# LPCB235_-_RM48_-_100BASET.net
KiCad netlist of a schematic drawn in Altium Designer
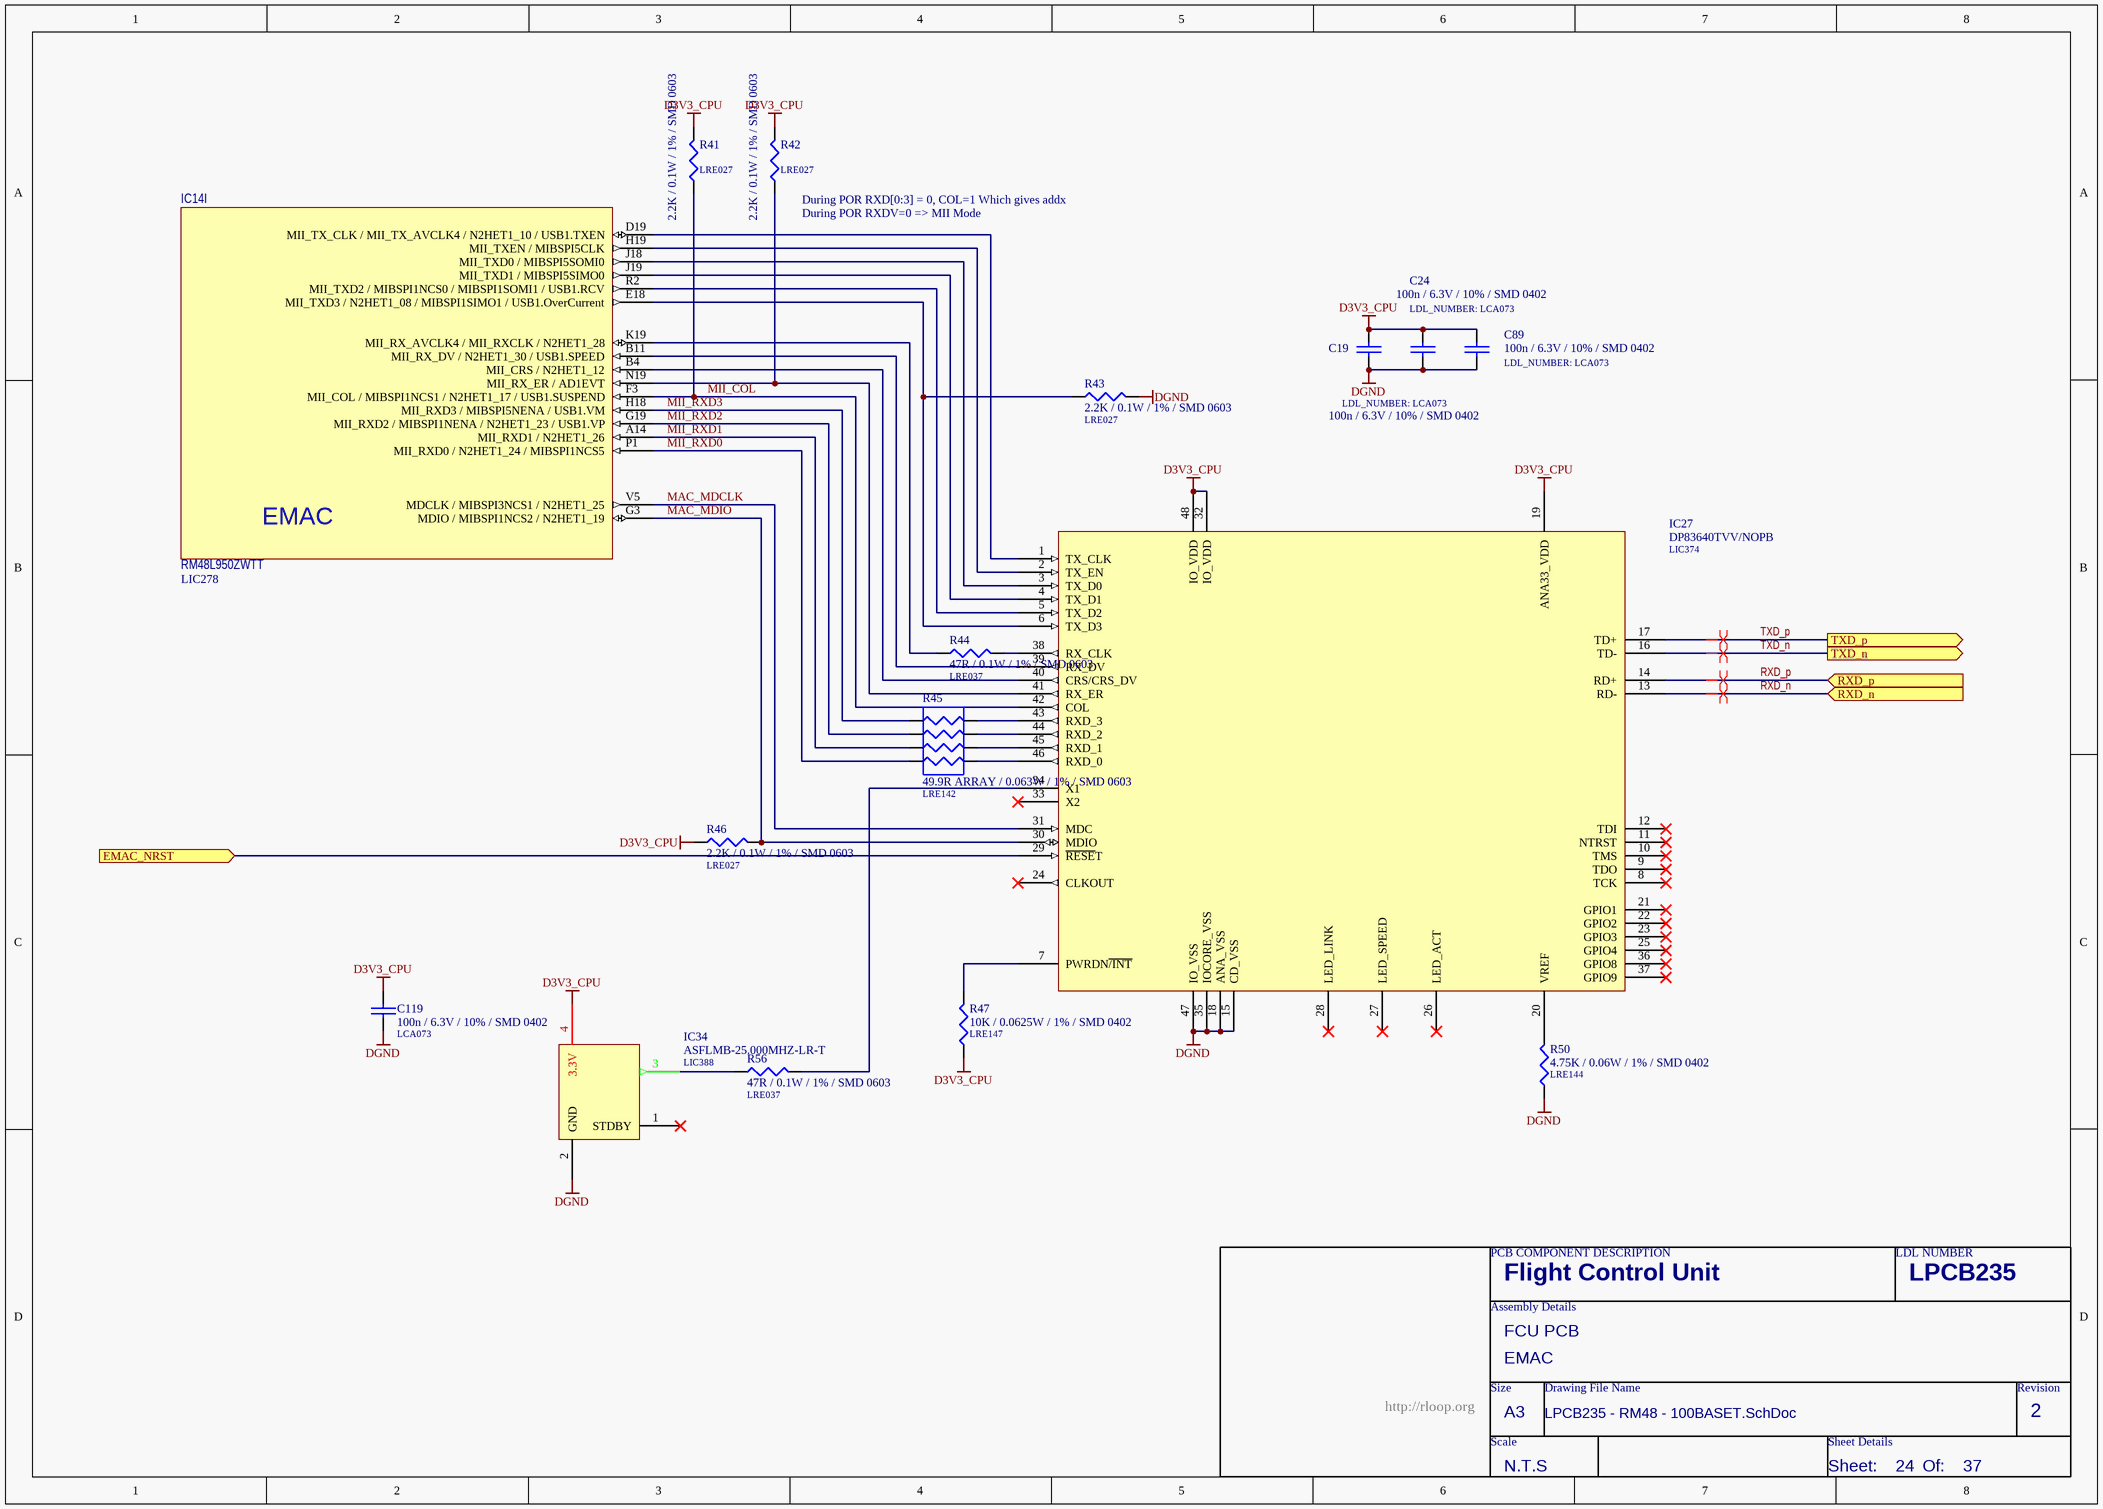
[diagram p0: LPCB235 - RM48 - 100BASET.SchDoc]

(export (version "E")
  (design (tool "Eeschema 10.0.6"))
  (components
    (comp (ref "C19")
      (value "100n / 6.3V / 10% / SMD 0402")
      (footprint "LFP012__CC1005-0402-IPC7351_B")
      (description "Capacitor, Ceramic Chip, 100nF (0.1uF), 6.3V, 10%, SMD 0402 [LCA073]")
      (fields (field (name "LDL_NUMBER") "LCA073"))
      (libsource (lib "LDL_Capacitors") (part "100n / 6.3V / 10% / SMD 0402"))
    )
    (comp (ref "C24")
      (value "100n / 6.3V / 10% / SMD 0402")
      (footprint "LFP012__CC1005-0402-IPC7351_B")
      (description "Capacitor, Ceramic Chip, 100nF (0.1uF), 6.3V, 10%, SMD 0402 [LCA073]")
      (fields (field (name "LDL_NUMBER") "LCA073"))
      (libsource (lib "LDL_Capacitors") (part "100n / 6.3V / 10% / SMD 0402"))
    )
    (comp (ref "C89")
      (value "100n / 6.3V / 10% / SMD 0402")
      (footprint "LFP012__CC1005-0402-IPC7351_B")
      (description "Capacitor, Ceramic Chip, 100nF (0.1uF), 6.3V, 10%, SMD 0402 [LCA073]")
      (fields (field (name "LDL_NUMBER") "LCA073"))
      (libsource (lib "LDL_Capacitors") (part "100n / 6.3V / 10% / SMD 0402"))
    )
    (comp (ref "C119")
      (value "100n / 6.3V / 10% / SMD 0402")
      (footprint "LFP012__CC1005-0402-IPC7351_B")
      (description "Capacitor, Ceramic Chip, 100nF (0.1uF), 6.3V, 10%, SMD 0402 [LCA073]")
      (fields (field (name "LDL_NUMBER") "LCA073"))
      (libsource (lib "LDL_Capacitors") (part "100n / 6.3V / 10% / SMD 0402"))
    )
    (comp (ref "IC14")
      (value "RM48L950ZWTT")
      (footprint "LFP054__ZWT (S-PBGA-N337)")
      (description "IC, CPU, RM48 Safety CPU, SMD NFBGA337 [LIC278]")
      (fields (field (name "LDL_NUMBER") "LIC278"))
      (libsource (lib "LDL_Semiconductors") (part "RM48L950ZWTT"))
    )
    (comp (ref "IC27")
      (value "DP83640TVV/NOPB")
      (footprint "LFP058__F-QFP7X7-G48")
      (description "IC, Ethernet Transceiver, Precision Real Time Protocol, SMD LQFP48 [LIC374]")
      (fields (field (name "LDL_NUMBER") "LIC374"))
      (libsource (lib "LDL_Semiconductors") (part "DP83640TVV/NOPB"))
    )
    (comp (ref "IC34")
      (value "ASFLMB-25.000MHZ-LR-T")
      (footprint "LFP072__ASFLMB")
      (description "IC, Oscillator Module, 25MHz, 3.3V, SMD [LIC388]")
      (fields (field (name "LDL_NUMBER") "LIC388"))
      (libsource (lib "LDL_Semiconductors") (part "ASFLMB-25.000MHZ-LR-T"))
    )
    (comp (ref "R41")
      (value "2.2K / 0.1W / 1% / SMD 0603")
      (footprint "LFP020__CR1608-0603-IPC7351_B")
      (description "Resistor, Ceramic Chip, 2.2K, 0.1W, 1%, SMD 0603 [LRE027]")
      (fields (field (name "LDL_NUMBER") "LRE027"))
      (libsource (lib "LDL_Resistors") (part "2.2K / 0.1W / 1% / SMD 0603"))
    )
    (comp (ref "R42")
      (value "2.2K / 0.1W / 1% / SMD 0603")
      (footprint "LFP020__CR1608-0603-IPC7351_B")
      (description "Resistor, Ceramic Chip, 2.2K, 0.1W, 1%, SMD 0603 [LRE027]")
      (fields (field (name "LDL_NUMBER") "LRE027"))
      (libsource (lib "LDL_Resistors") (part "2.2K / 0.1W / 1% / SMD 0603"))
    )
    (comp (ref "R43")
      (value "2.2K / 0.1W / 1% / SMD 0603")
      (footprint "LFP020__CR1608-0603-IPC7351_B")
      (description "Resistor, Ceramic Chip, 2.2K, 0.1W, 1%, SMD 0603 [LRE027]")
      (fields (field (name "LDL_NUMBER") "LRE027"))
      (libsource (lib "LDL_Resistors") (part "2.2K / 0.1W / 1% / SMD 0603"))
    )
    (comp (ref "R44")
      (value "47R / 0.1W / 1% / SMD 0603")
      (footprint "LFP020__CR1608-0603-IPC7351_B")
      (description "Resistor, Ceramic Chip, 47R, 0.1W, 1%, SMD 0603 [LRE037]")
      (fields (field (name "LDL_NUMBER") "LRE037"))
      (libsource (lib "LDL_Resistors") (part "47R / 0.1W / 1% / SMD 0603"))
    )
    (comp (ref "R45")
      (value "49.9R ARRAY / 0.063W / 1% / SMD 0603")
      (footprint "LFP065__RESPACK4-0603")
      (description "Resistor, Array, 49.9R, 0.063W, 1%, SMD 0603 [LRE142]")
      (fields (field (name "LDL_NUMBER") "LRE142"))
      (libsource (lib "LDL_Resistors") (part "49.9R ARRAY / 0.063W / 1% / SMD 0603"))
    )
    (comp (ref "R46")
      (value "2.2K / 0.1W / 1% / SMD 0603")
      (footprint "LFP020__CR1608-0603-IPC7351_B")
      (description "Resistor, Ceramic Chip, 2.2K, 0.1W, 1%, SMD 0603 [LRE027]")
      (fields (field (name "LDL_NUMBER") "LRE027"))
      (libsource (lib "LDL_Resistors") (part "2.2K / 0.1W / 1% / SMD 0603"))
    )
    (comp (ref "R47")
      (value "10K / 0.0625W / 1% / SMD 0402")
      (footprint "LFP030__CR1005-0402-IPC7351")
      (description "Resistor, Ceramic Chip, 10K, 0.0625W, 1%, SMD 0402 [LRE147]")
      (fields (field (name "LDL_NUMBER") "LRE147"))
      (libsource (lib "LDL_Resistors") (part "10K / 0.0625W / 1% / SMD 0402"))
    )
    (comp (ref "R50")
      (value "4.75K / 0.06W / 1% / SMD 0402")
      (footprint "LFP030__CR1005-0402-IPC7351")
      (description "Resistor, Ceramic Chip, 4.75K, 0.0625W, 1%, SMD 0402 [LRE144]")
      (fields (field (name "LDL_NUMBER") "LRE144"))
      (libsource (lib "LDL_Resistors") (part "4.75K / 0.06W / 1% / SMD 0402"))
    )
    (comp (ref "R56")
      (value "47R / 0.1W / 1% / SMD 0603")
      (footprint "LFP020__CR1608-0603-IPC7351_B")
      (description "Resistor, Ceramic Chip, 47R, 0.1W, 1%, SMD 0603 [LRE037]")
      (fields (field (name "LDL_NUMBER") "LRE037"))
      (libsource (lib "LDL_Resistors") (part "47R / 0.1W / 1% / SMD 0603"))
    )
  )
  (nets
    (net (code "1") (name "/EMAC_NRST") (class "Default")
      (node (ref "IC27") (pin "29") (pinfunction "~{RESE}T_29") (pintype "input"))
    )
    (net (code "2") (name "/MAC_MDCLK") (class "Default")
      (node (ref "IC14") (pin "V5") (pinfunction "MDCLK_/_MIBSPI3NCS1_/_N2HET1_25_V5") (pintype "output"))
      (node (ref "IC27") (pin "31") (pinfunction "MDC_31") (pintype "input"))
    )
    (net (code "3") (name "/MAC_MDIO") (class "Default")
      (node (ref "IC14") (pin "G3") (pinfunction "MDIO_/_MIBSPI1NCS2_/_N2HET1_19_G3") (pintype "bidirectional"))
      (node (ref "IC27") (pin "30") (pinfunction "MDIO_30") (pintype "bidirectional"))
      (node (ref "R46") (pin "2") (pintype "passive"))
    )
    (net (code "4") (name "/MII_COL") (class "Default")
      (node (ref "IC14") (pin "F3") (pinfunction "MII_COL_/_MIBSPI1NCS1_/_N2HET1_17_/_USB1.SUSPEND_F3") (pintype "input"))
      (node (ref "IC27") (pin "42") (pinfunction "COL_42") (pintype "output"))
      (node (ref "R41") (pin "1") (pintype "passive"))
    )
    (net (code "5") (name "/MII_RXD0") (class "Default")
      (node (ref "IC14") (pin "P1") (pinfunction "MII_RXD0_/_N2HET1_24_/_MIBSPI1NCS5_P1") (pintype "input"))
      (node (ref "R45") (pin "4") (pintype "passive"))
    )
    (net (code "6") (name "/MII_RXD1") (class "Default")
      (node (ref "IC14") (pin "A14") (pinfunction "MII_RXD1_/_N2HET1_26_A14") (pintype "input"))
      (node (ref "R45") (pin "3") (pintype "passive"))
    )
    (net (code "7") (name "/MII_RXD2") (class "Default")
      (node (ref "IC14") (pin "G19") (pinfunction "MII_RXD2_/_MIBSPI1NENA_/_N2HET1_23_/_USB1.VP_G19") (pintype "input"))
      (node (ref "R45") (pin "2") (pintype "passive"))
    )
    (net (code "8") (name "/MII_RXD3") (class "Default")
      (node (ref "IC14") (pin "H18") (pinfunction "MII_RXD3_/_MIBSPI5NENA_/_USB1.VM_H18") (pintype "input"))
      (node (ref "R45") (pin "1") (pintype "passive"))
    )
    (net (code "9") (name "/RXD_n") (class "Default")
      (node (ref "IC27") (pin "13") (pinfunction "RD-_13") (pintype "passive"))
    )
    (net (code "10") (name "/RXD_p") (class "Default")
      (node (ref "IC27") (pin "14") (pinfunction "RD+_14") (pintype "passive"))
    )
    (net (code "11") (name "/TXD_n") (class "Default")
      (node (ref "IC27") (pin "16") (pinfunction "TD-_16") (pintype "passive"))
    )
    (net (code "12") (name "/TXD_p") (class "Default")
      (node (ref "IC27") (pin "17") (pinfunction "TD+_17") (pintype "passive"))
    )
    (net (code "13") (name "D3V3_CPU") (class "Default")
      (node (ref "C119") (pin "1") (pintype "passive"))
      (node (ref "C19") (pin "1") (pintype "passive"))
      (node (ref "C24") (pin "1") (pintype "passive"))
      (node (ref "C89") (pin "1") (pintype "passive"))
      (node (ref "IC27") (pin "19") (pinfunction "ANA33_VDD_19") (pintype "power_in"))
      (node (ref "IC27") (pin "32") (pinfunction "IO_VDD_32") (pintype "power_in"))
      (node (ref "IC27") (pin "48") (pinfunction "IO_VDD_48") (pintype "power_in"))
      (node (ref "IC34") (pin "4") (pinfunction "3.3V_4") (pintype "power_in"))
      (node (ref "R41") (pin "2") (pintype "passive"))
      (node (ref "R42") (pin "2") (pintype "passive"))
      (node (ref "R46") (pin "1") (pintype "passive"))
      (node (ref "R47") (pin "1") (pintype "passive"))
    )
    (net (code "14") (name "DGND") (class "Default")
      (node (ref "C119") (pin "2") (pintype "passive"))
      (node (ref "C19") (pin "2") (pintype "passive"))
      (node (ref "C24") (pin "2") (pintype "passive"))
      (node (ref "C89") (pin "2") (pintype "passive"))
      (node (ref "IC27") (pin "15") (pinfunction "CD_VSS_15") (pintype "power_in"))
      (node (ref "IC27") (pin "18") (pinfunction "ANA_VSS_18") (pintype "power_in"))
      (node (ref "IC27") (pin "35") (pinfunction "IOCORE_VSS_35") (pintype "power_in"))
      (node (ref "IC27") (pin "47") (pinfunction "IO_VSS_47") (pintype "power_in"))
      (node (ref "IC34") (pin "2") (pinfunction "GND_2") (pintype "power_in"))
      (node (ref "R43") (pin "2") (pintype "passive"))
      (node (ref "R50") (pin "1") (pintype "passive"))
    )
    (net (code "15") (name "Net-(IC14I-MII_CRS_{slash}_N2HET1_12)") (class "Default")
      (node (ref "IC14") (pin "B4") (pinfunction "MII_CRS_/_N2HET1_12_B4") (pintype "input"))
      (node (ref "IC27") (pin "40") (pinfunction "CRS/CRS_DV_40") (pintype "output"))
    )
    (net (code "16") (name "Net-(IC14I-MII_RX_AVCLK4_{slash}_MII_RXCLK_{slash}_N2HET1_28)") (class "Default")
      (node (ref "IC14") (pin "K19") (pinfunction "MII_RX_AVCLK4_/_MII_RXCLK_/_N2HET1_28_K19") (pintype "bidirectional"))
      (node (ref "R44") (pin "1") (pintype "passive"))
    )
    (net (code "17") (name "Net-(IC14I-MII_RX_DV_{slash}_N2HET1_30_{slash}_USB1.SPEED)") (class "Default")
      (node (ref "IC14") (pin "B11") (pinfunction "MII_RX_DV_/_N2HET1_30_/_USB1.SPEED_B11") (pintype "input"))
      (node (ref "IC27") (pin "39") (pinfunction "RX_DV_39") (pintype "output"))
    )
    (net (code "18") (name "Net-(IC14I-MII_RX_ER_{slash}_AD1EVT)") (class "Default")
      (node (ref "IC14") (pin "N19") (pinfunction "MII_RX_ER_/_AD1EVT_N19") (pintype "input"))
      (node (ref "IC27") (pin "41") (pinfunction "RX_ER_41") (pintype "output"))
      (node (ref "R42") (pin "1") (pintype "passive"))
    )
    (net (code "19") (name "Net-(IC14I-MII_TXD0_{slash}_MIBSPI5SOMI0)") (class "Default")
      (node (ref "IC14") (pin "J18") (pinfunction "MII_TXD0_/_MIBSPI5SOMI0_J18") (pintype "output"))
      (node (ref "IC27") (pin "3") (pinfunction "TX_D0_3") (pintype "input"))
    )
    (net (code "20") (name "Net-(IC14I-MII_TXD1_{slash}_MIBSPI5SIMO0)") (class "Default")
      (node (ref "IC14") (pin "J19") (pinfunction "MII_TXD1_/_MIBSPI5SIMO0_J19") (pintype "output"))
      (node (ref "IC27") (pin "4") (pinfunction "TX_D1_4") (pintype "input"))
    )
    (net (code "21") (name "Net-(IC14I-MII_TXD2_{slash}_MIBSPI1NCS0_{slash}_MIBSPI1SOMI1_{slash}_USB1.RCV)") (class "Default")
      (node (ref "IC14") (pin "R2") (pinfunction "MII_TXD2_/_MIBSPI1NCS0_/_MIBSPI1SOMI1_/_USB1.RCV_R2") (pintype "output"))
      (node (ref "IC27") (pin "5") (pinfunction "TX_D2_5") (pintype "input"))
    )
    (net (code "22") (name "Net-(IC14I-MII_TXD3_{slash}_N2HET1_08_{slash}_MIBSPI1SIMO1_{slash}_USB1.OverCurrent)") (class "Default")
      (node (ref "IC14") (pin "E18") (pinfunction "MII_TXD3_/_N2HET1_08_/_MIBSPI1SIMO1_/_USB1.OverCurrent_E18") (pintype "output"))
      (node (ref "IC27") (pin "6") (pinfunction "TX_D3_6") (pintype "input"))
      (node (ref "R43") (pin "1") (pintype "passive"))
    )
    (net (code "23") (name "Net-(IC14I-MII_TXEN_{slash}_MIBSPI5CLK)") (class "Default")
      (node (ref "IC14") (pin "H19") (pinfunction "MII_TXEN_/_MIBSPI5CLK_H19") (pintype "output"))
      (node (ref "IC27") (pin "2") (pinfunction "TX_EN_2") (pintype "input"))
    )
    (net (code "24") (name "Net-(IC14I-MII_TX_CLK_{slash}_MII_TX_AVCLK4_{slash}_N2HET1_10_{slash}_USB1.TXEN)") (class "Default")
      (node (ref "IC14") (pin "D19") (pinfunction "MII_TX_CLK_/_MII_TX_AVCLK4_/_N2HET1_10_/_USB1.TXEN_D19") (pintype "bidirectional"))
      (node (ref "IC27") (pin "1") (pinfunction "TX_CLK_1") (pintype "input"))
    )
    (net (code "25") (name "Net-(IC27-PWRDN~{{slash}INT})") (class "Default")
      (node (ref "IC27") (pin "7") (pinfunction "PWRDN~{/INT}_7") (pintype "passive"))
      (node (ref "R47") (pin "2") (pintype "passive"))
    )
    (net (code "26") (name "Net-(IC27-RXD_0)") (class "Default")
      (node (ref "IC27") (pin "46") (pinfunction "RXD_0_46") (pintype "output"))
      (node (ref "R45") (pin "5") (pintype "passive"))
    )
    (net (code "27") (name "Net-(IC27-RXD_1)") (class "Default")
      (node (ref "IC27") (pin "45") (pinfunction "RXD_1_45") (pintype "output"))
      (node (ref "R45") (pin "6") (pintype "passive"))
    )
    (net (code "28") (name "Net-(IC27-RXD_2)") (class "Default")
      (node (ref "IC27") (pin "44") (pinfunction "RXD_2_44") (pintype "output"))
      (node (ref "R45") (pin "7") (pintype "passive"))
    )
    (net (code "29") (name "Net-(IC27-RXD_3)") (class "Default")
      (node (ref "IC27") (pin "43") (pinfunction "RXD_3_43") (pintype "output"))
      (node (ref "R45") (pin "8") (pintype "passive"))
    )
    (net (code "30") (name "Net-(IC27-RX_CLK)") (class "Default")
      (node (ref "IC27") (pin "38") (pinfunction "RX_CLK_38") (pintype "output"))
      (node (ref "R44") (pin "2") (pintype "passive"))
    )
    (net (code "31") (name "Net-(IC27-VREF)") (class "Default")
      (node (ref "IC27") (pin "20") (pinfunction "VREF_20") (pintype "passive"))
      (node (ref "R50") (pin "2") (pintype "passive"))
    )
    (net (code "32") (name "Net-(IC27-X1)") (class "Default")
      (node (ref "IC27") (pin "34") (pinfunction "X1_34") (pintype "passive"))
      (node (ref "R56") (pin "2") (pintype "passive"))
    )
    (net (code "33") (name "Net-(IC34-OUT)") (class "Default")
      (node (ref "IC34") (pin "3") (pinfunction "OUT_3") (pintype "output"))
      (node (ref "R56") (pin "1") (pintype "passive"))
    )
    (net (code "34") (name "unconnected-(IC27-CLKOUT-Pad24)") (class "Default")
      (node (ref "IC27") (pin "24") (pinfunction "CLKOUT_24") (pintype "output+no_connect"))
    )
    (net (code "35") (name "unconnected-(IC27-GPIO1-Pad21)") (class "Default")
      (node (ref "IC27") (pin "21") (pinfunction "GPIO1_21") (pintype "passive+no_connect"))
    )
    (net (code "36") (name "unconnected-(IC27-GPIO2-Pad22)") (class "Default")
      (node (ref "IC27") (pin "22") (pinfunction "GPIO2_22") (pintype "passive+no_connect"))
    )
    (net (code "37") (name "unconnected-(IC27-GPIO3-Pad23)") (class "Default")
      (node (ref "IC27") (pin "23") (pinfunction "GPIO3_23") (pintype "passive+no_connect"))
    )
    (net (code "38") (name "unconnected-(IC27-GPIO4-Pad25)") (class "Default")
      (node (ref "IC27") (pin "25") (pinfunction "GPIO4_25") (pintype "passive+no_connect"))
    )
    (net (code "39") (name "unconnected-(IC27-GPIO8-Pad36)") (class "Default")
      (node (ref "IC27") (pin "36") (pinfunction "GPIO8_36") (pintype "passive+no_connect"))
    )
    (net (code "40") (name "unconnected-(IC27-GPIO9-Pad37)") (class "Default")
      (node (ref "IC27") (pin "37") (pinfunction "GPIO9_37") (pintype "passive+no_connect"))
    )
    (net (code "41") (name "unconnected-(IC27-LED_ACT-Pad26)") (class "Default")
      (node (ref "IC27") (pin "26") (pinfunction "LED_ACT_26") (pintype "passive+no_connect"))
    )
    (net (code "42") (name "unconnected-(IC27-LED_LINK-Pad28)") (class "Default")
      (node (ref "IC27") (pin "28") (pinfunction "LED_LINK_28") (pintype "passive+no_connect"))
    )
    (net (code "43") (name "unconnected-(IC27-LED_SPEED-Pad27)") (class "Default")
      (node (ref "IC27") (pin "27") (pinfunction "LED_SPEED_27") (pintype "passive+no_connect"))
    )
    (net (code "44") (name "unconnected-(IC27-NTRST-Pad11)") (class "Default")
      (node (ref "IC27") (pin "11") (pinfunction "NTRST_11") (pintype "passive+no_connect"))
    )
    (net (code "45") (name "unconnected-(IC27-TCK-Pad8)") (class "Default")
      (node (ref "IC27") (pin "8") (pinfunction "TCK_8") (pintype "passive+no_connect"))
    )
    (net (code "46") (name "unconnected-(IC27-TDI-Pad12)") (class "Default")
      (node (ref "IC27") (pin "12") (pinfunction "TDI_12") (pintype "passive+no_connect"))
    )
    (net (code "47") (name "unconnected-(IC27-TDO-Pad9)") (class "Default")
      (node (ref "IC27") (pin "9") (pinfunction "TDO_9") (pintype "passive+no_connect"))
    )
    (net (code "48") (name "unconnected-(IC27-TMS-Pad10)") (class "Default")
      (node (ref "IC27") (pin "10") (pinfunction "TMS_10") (pintype "passive+no_connect"))
    )
    (net (code "49") (name "unconnected-(IC27-X2-Pad33)") (class "Default")
      (node (ref "IC27") (pin "33") (pinfunction "X2_33") (pintype "passive+no_connect"))
    )
    (net (code "50") (name "unconnected-(IC34-STDBY-Pad1)") (class "Default")
      (node (ref "IC34") (pin "1") (pinfunction "STDBY_1") (pintype "passive+no_connect"))
    )
  )
)
